# o_clone_rev_d.net
KiCad netlist of a schematic drawn in EAGLE
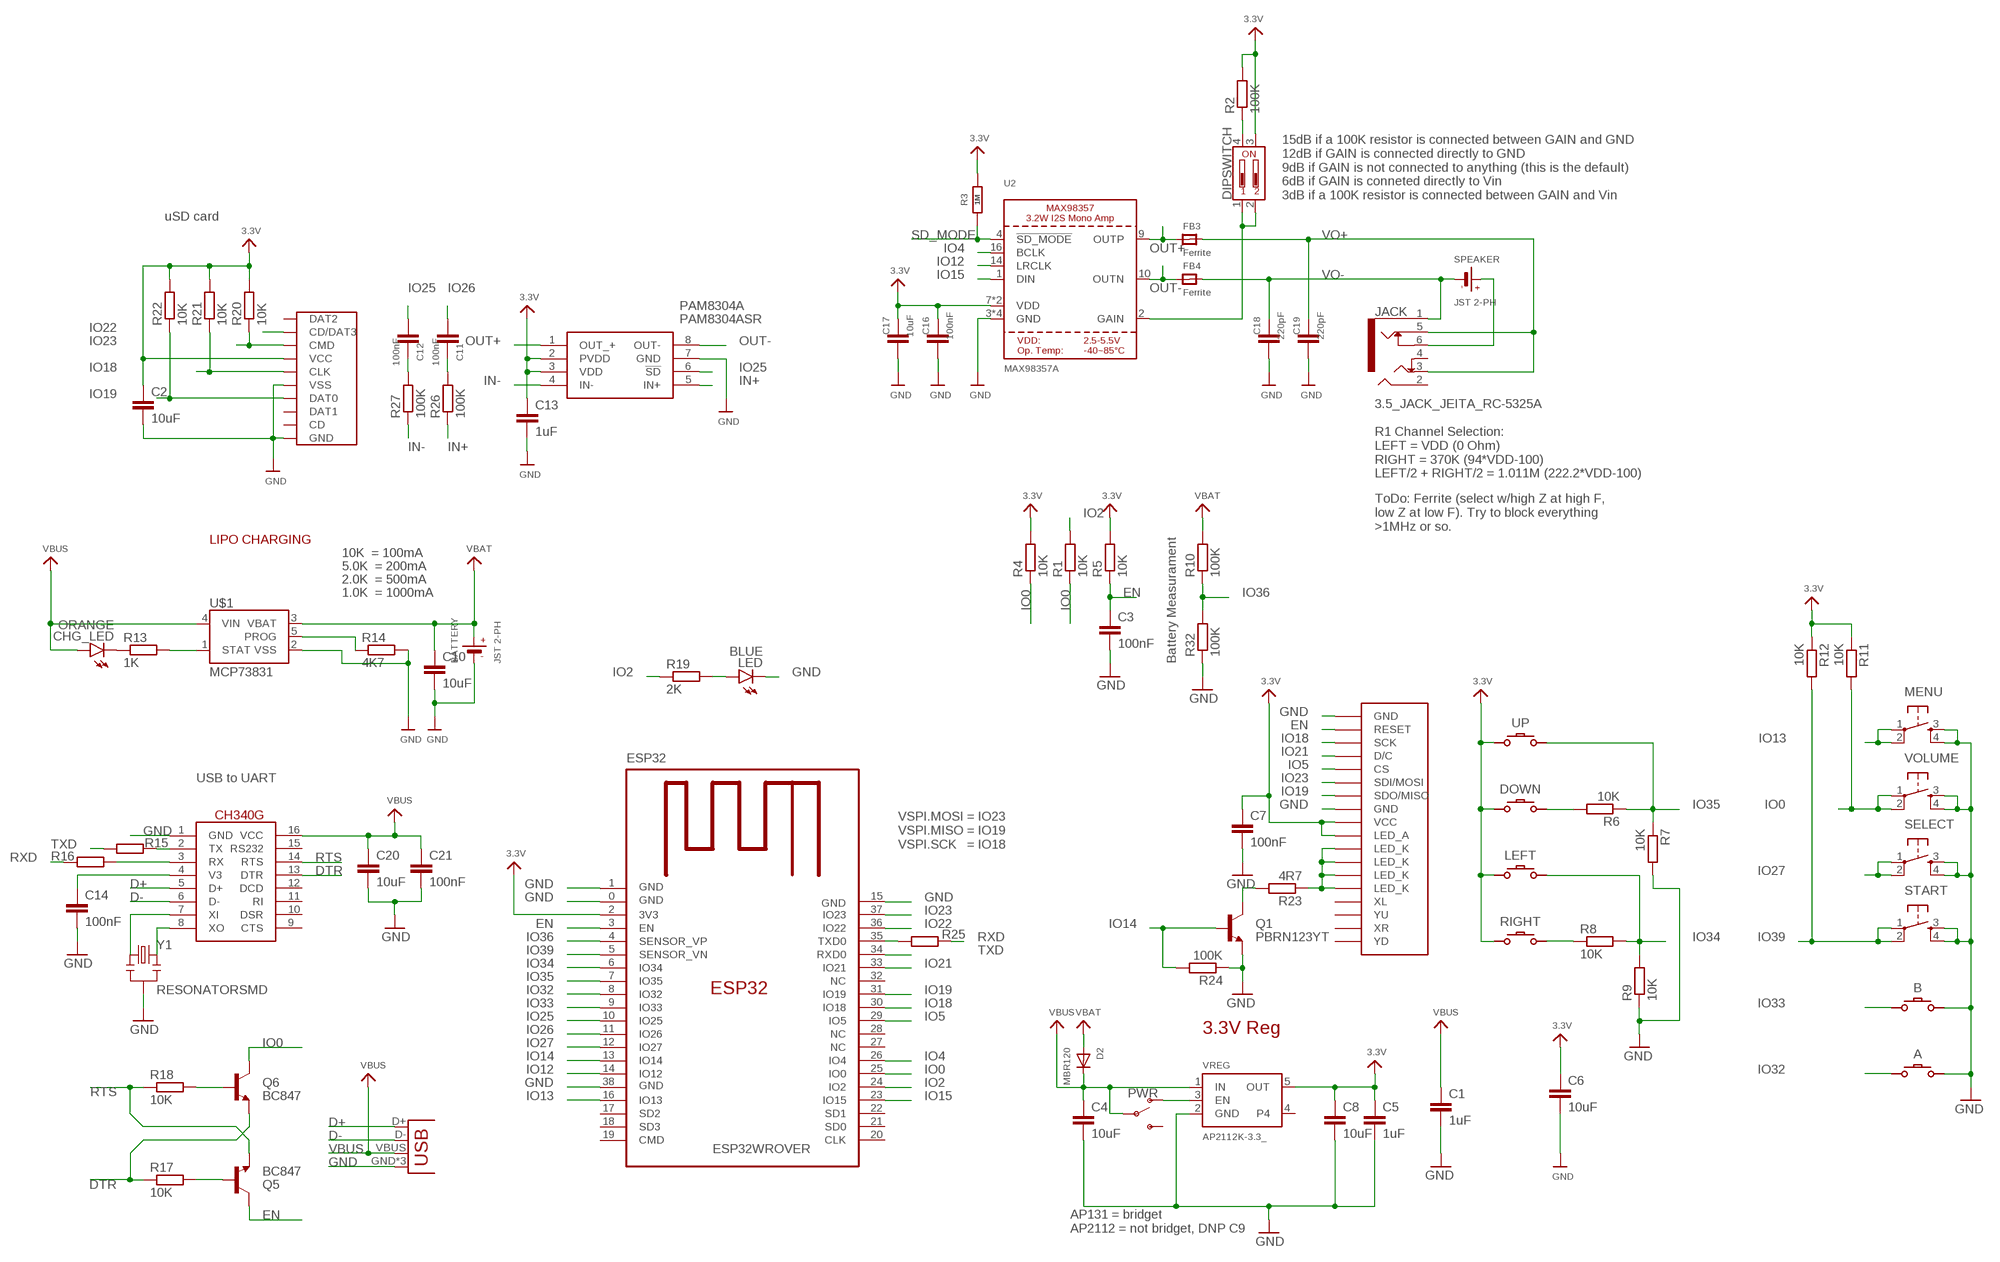
[diagram p0: schematic, sheet 1]

(export (version "E")
  (design (tool "Eeschema 10.0.6"))
  (components
    (comp (ref "A")
      (value "CONDUCTIVE_BUTTON")
      (footprint "eagle-import:CONDUCTIVE_BUTTON")
      (libsource (lib "eagle-import") (part "CONDUCTIVE_BUTTON"))
    )
    (comp (ref "B")
      (value "CONDUCTIVE_BUTTON")
      (footprint "eagle-import:CONDUCTIVE_BUTTON")
      (libsource (lib "eagle-import") (part "CONDUCTIVE_BUTTON"))
    )
    (comp (ref "BATTERY")
      (value "JST 2-PH")
      (footprint "eagle-import:JSTPH2")
      (libsource (lib "eagle-import") (part "JST_CONNECTOR"))
    )
    (comp (ref "C1")
      (value "1uF")
      (footprint "eagle-import:C0805K")
      (libsource (lib "eagle-import") (part "C-EUC0805K"))
    )
    (comp (ref "C2")
      (value "10uF")
      (footprint "eagle-import:C0805K")
      (libsource (lib "eagle-import") (part "C-EUC0805K"))
    )
    (comp (ref "C3")
      (value "100nF")
      (footprint "eagle-import:C0805K")
      (libsource (lib "eagle-import") (part "C-EUC0805K"))
    )
    (comp (ref "C4")
      (value "10uF")
      (footprint "eagle-import:C0805K")
      (libsource (lib "eagle-import") (part "C-EUC0805K"))
    )
    (comp (ref "C5")
      (value "1uF")
      (footprint "eagle-import:C0805K")
      (libsource (lib "eagle-import") (part "C-EUC0805K"))
    )
    (comp (ref "C6")
      (value "10uF")
      (footprint "eagle-import:C0805K")
      (libsource (lib "eagle-import") (part "C-EUC0805K"))
    )
    (comp (ref "C7")
      (value "100nF")
      (footprint "eagle-import:C0805")
      (libsource (lib "eagle-import") (part "C-EUC0805"))
    )
    (comp (ref "C8")
      (value "10uF")
      (footprint "eagle-import:C0805K")
      (libsource (lib "eagle-import") (part "C-EUC0805K"))
    )
    (comp (ref "C10")
      (value "10uF")
      (footprint "eagle-import:C0805K")
      (libsource (lib "eagle-import") (part "C-EUC0805K"))
    )
    (comp (ref "C11")
      (value "100nF")
      (footprint "eagle-import:C0805K")
      (libsource (lib "eagle-import") (part "C-EUC0805K"))
    )
    (comp (ref "C12")
      (value "100nF")
      (footprint "eagle-import:C0805K")
      (libsource (lib "eagle-import") (part "C-EUC0805K"))
    )
    (comp (ref "C13")
      (value "1uF")
      (footprint "eagle-import:C0805K")
      (libsource (lib "eagle-import") (part "C-EUC0805K"))
    )
    (comp (ref "C14")
      (value "100nF")
      (footprint "eagle-import:C0805K")
      (libsource (lib "eagle-import") (part "C-EUC0805K"))
    )
    (comp (ref "C16")
      (value "100nF")
      (footprint "eagle-import:C0805K")
      (libsource (lib "eagle-import") (part "C-EUC0805K"))
    )
    (comp (ref "C17")
      (value "10uF")
      (footprint "eagle-import:C0805K")
      (libsource (lib "eagle-import") (part "C-EUC0805K"))
    )
    (comp (ref "C18")
      (value "220pF")
      (footprint "eagle-import:C0805K")
      (libsource (lib "eagle-import") (part "C-EUC0805K"))
    )
    (comp (ref "C19")
      (value "220pF")
      (footprint "eagle-import:C0805K")
      (libsource (lib "eagle-import") (part "C-EUC0805K"))
    )
    (comp (ref "C20")
      (value "10uF")
      (footprint "eagle-import:C0805K")
      (libsource (lib "eagle-import") (part "C-EUC0805K"))
    )
    (comp (ref "C21")
      (value "100nF")
      (footprint "eagle-import:C0805K")
      (libsource (lib "eagle-import") (part "C-EUC0805K"))
    )
    (comp (ref "CHG_LED")
      (value "ORANGE")
      (footprint "eagle-import:CHIPLED_0805")
      (libsource (lib "eagle-import") (part "LEDCHIPLED_0805"))
    )
    (comp (ref "D2")
      (value "MBR120")
      (footprint "eagle-import:SOD-123")
      (libsource (lib "eagle-import") (part "DIODESOD-123"))
    )
    (comp (ref "DIPSWITCH")
      (value "DIP-02-SMD-50MIL")
      (footprint "eagle-import:DIPSWITCH-02-50MIL")
      (libsource (lib "eagle-import") (part "DIP-02-SMD-50MIL"))
    )
    (comp (ref "DOWN")
      (value "CONDUCTIVE_BUTTON")
      (footprint "eagle-import:CONDUCTIVE_BUTTON")
      (libsource (lib "eagle-import") (part "CONDUCTIVE_BUTTON"))
    )
    (comp (ref "ESP32")
      (value "ESP32WROVER")
      (footprint "eagle-import:ESP32WROVER")
      (libsource (lib "eagle-import") (part "ESP32WROVER"))
    )
    (comp (ref "FB3")
      (value "Ferrite")
      (footprint "eagle-import:0805")
      (libsource (lib "eagle-import") (part "FERRITE0805"))
    )
    (comp (ref "FB4")
      (value "Ferrite")
      (footprint "eagle-import:0805")
      (libsource (lib "eagle-import") (part "FERRITE0805"))
    )
    (comp (ref "JACK")
      (value "3.5_JACK_JEITA_RC-5325A")
      (footprint "eagle-import:3.5_JACK_JEITA_RC-5325A")
      (libsource (lib "eagle-import") (part "3.5_JACK_JEITA_RC-5325A"))
    )
    (comp (ref "LCD")
      (value "ILI9341_3.2LCD_")
      (footprint "eagle-import:LI9341_3.2LCD")
      (libsource (lib "eagle-import") (part "ILI9341_3.2LCD_"))
    )
    (comp (ref "LED")
      (value "BLUE")
      (footprint "eagle-import:CHIPLED_0805")
      (libsource (lib "eagle-import") (part "LEDCHIPLED_0805"))
    )
    (comp (ref "LEFT")
      (value "CONDUCTIVE_BUTTON")
      (footprint "eagle-import:CONDUCTIVE_BUTTON")
      (libsource (lib "eagle-import") (part "CONDUCTIVE_BUTTON"))
    )
    (comp (ref "MENU")
      (value "TACTILE_SWITCHE_5X5_MICRO\"")
      (footprint "eagle-import:TACTILE_SWITCH_5X5_MICRO")
      (libsource (lib "eagle-import") (part "TACTILE_SWITCHE_5X5_MICRO{dblquote}"))
    )
    (comp (ref "PAM8304A")
      (value "PAM8304ASR")
      (footprint "eagle-import:SOP65P490X110-8N")
      (fields (field (name "MOUSER_PART_NUMBER") "621-PAM8304ASR"))
      (libsource (lib "eagle-import") (part "PAM8304ASR"))
    )
    (comp (ref "PWR")
      (value "SWITCH-SPDT-SMD-RIGHT-ANGLE")
      (footprint "eagle-import:SWITCH_SPST_SMD_A")
      (libsource (lib "eagle-import") (part "SWITCH-SPDT-SMD-RIGHT-ANGLE"))
    )
    (comp (ref "Q1")
      (value "PBRN123YT")
      (footprint "eagle-import:SOT23-3")
      (libsource (lib "eagle-import") (part "TRANSISTOR_NPNSOT23-3"))
    )
    (comp (ref "Q5")
      (value "BC847")
      (footprint "eagle-import:SOT23-3")
      (libsource (lib "eagle-import") (part "TRANSISTOR_NPNSOT23-3"))
    )
    (comp (ref "Q6")
      (value "BC847")
      (footprint "eagle-import:SOT23-3")
      (libsource (lib "eagle-import") (part "TRANSISTOR_NPNSOT23-3"))
    )
    (comp (ref "R1")
      (value "10K")
      (footprint "eagle-import:R0805")
      (libsource (lib "eagle-import") (part "R-EU_R0805"))
    )
    (comp (ref "R2")
      (value "100K")
      (footprint "eagle-import:R0805")
      (libsource (lib "eagle-import") (part "R-EU_R0805"))
    )
    (comp (ref "R3")
      (value "1M")
      (footprint "eagle-import:R0805")
      (libsource (lib "eagle-import") (part "R-EU_R0805"))
    )
    (comp (ref "R4")
      (value "10K")
      (footprint "eagle-import:R0805")
      (libsource (lib "eagle-import") (part "R-EU_R0805"))
    )
    (comp (ref "R5")
      (value "10K")
      (footprint "eagle-import:R0805")
      (libsource (lib "eagle-import") (part "R-EU_R0805"))
    )
    (comp (ref "R6")
      (value "10K")
      (footprint "eagle-import:R0805")
      (libsource (lib "eagle-import") (part "R-EU_R0805"))
    )
    (comp (ref "R7")
      (value "10K")
      (footprint "eagle-import:R0805")
      (libsource (lib "eagle-import") (part "R-EU_R0805"))
    )
    (comp (ref "R8")
      (value "10K")
      (footprint "eagle-import:R0805")
      (libsource (lib "eagle-import") (part "R-EU_R0805"))
    )
    (comp (ref "R9")
      (value "10K")
      (footprint "eagle-import:R0805")
      (libsource (lib "eagle-import") (part "R-EU_R0805"))
    )
    (comp (ref "R10")
      (value "100K")
      (footprint "eagle-import:R0805")
      (libsource (lib "eagle-import") (part "R-EU_R0805"))
    )
    (comp (ref "R11")
      (value "10K")
      (footprint "eagle-import:R0805")
      (libsource (lib "eagle-import") (part "R-EU_R0805"))
    )
    (comp (ref "R12")
      (value "10K")
      (footprint "eagle-import:R0805")
      (libsource (lib "eagle-import") (part "R-EU_R0805"))
    )
    (comp (ref "R13")
      (value "1K")
      (footprint "eagle-import:R0805")
      (libsource (lib "eagle-import") (part "R-EU_R0805"))
    )
    (comp (ref "R14")
      (value "4K7")
      (footprint "eagle-import:R0805")
      (libsource (lib "eagle-import") (part "R-EU_R0805"))
    )
    (comp (ref "R15")
      (value "470R")
      (footprint "eagle-import:R0805")
      (libsource (lib "eagle-import") (part "R-EU_R0805"))
    )
    (comp (ref "R16")
      (value "470R")
      (footprint "eagle-import:R0805")
      (libsource (lib "eagle-import") (part "R-EU_R0805"))
    )
    (comp (ref "R17")
      (value "10K")
      (footprint "eagle-import:R0805")
      (libsource (lib "eagle-import") (part "R-EU_R0805"))
    )
    (comp (ref "R18")
      (value "10K")
      (footprint "eagle-import:R0805")
      (libsource (lib "eagle-import") (part "R-EU_R0805"))
    )
    (comp (ref "R19")
      (value "2K")
      (footprint "eagle-import:R0805")
      (libsource (lib "eagle-import") (part "R-EU_R0805"))
    )
    (comp (ref "R20")
      (value "10K")
      (footprint "eagle-import:R0805")
      (libsource (lib "eagle-import") (part "R-EU_R0805"))
    )
    (comp (ref "R21")
      (value "10K")
      (footprint "eagle-import:R0805")
      (libsource (lib "eagle-import") (part "R-EU_R0805"))
    )
    (comp (ref "R22")
      (value "10K")
      (footprint "eagle-import:R0805")
      (libsource (lib "eagle-import") (part "R-EU_R0805"))
    )
    (comp (ref "R23")
      (value "4R7")
      (footprint "eagle-import:R0805")
      (libsource (lib "eagle-import") (part "R-EU_R0805"))
    )
    (comp (ref "R24")
      (value "100K")
      (footprint "eagle-import:R0805")
      (libsource (lib "eagle-import") (part "R-EU_R0805"))
    )
    (comp (ref "R25")
      (value "470R")
      (footprint "eagle-import:R0805")
      (libsource (lib "eagle-import") (part "R-EU_R0805"))
    )
    (comp (ref "R26")
      (value "100K")
      (footprint "eagle-import:R0805")
      (libsource (lib "eagle-import") (part "R-EU_R0805"))
    )
    (comp (ref "R27")
      (value "100K")
      (footprint "eagle-import:R0805")
      (libsource (lib "eagle-import") (part "R-EU_R0805"))
    )
    (comp (ref "R32")
      (value "100K")
      (footprint "eagle-import:R0805")
      (libsource (lib "eagle-import") (part "R-EU_R0805"))
    )
    (comp (ref "RIGHT")
      (value "CONDUCTIVE_BUTTON")
      (footprint "eagle-import:CONDUCTIVE_BUTTON")
      (libsource (lib "eagle-import") (part "CONDUCTIVE_BUTTON"))
    )
    (comp (ref "SD_CARD")
      (value "MICRO_SD_CARD\"")
      (footprint "eagle-import:TFP09-2--12B")
      (libsource (lib "eagle-import") (part "MICRO_SD_CARD{dblquote}"))
    )
    (comp (ref "SELECT")
      (value "TACTILE_SWITCHE_5X5_MICRO\"")
      (footprint "eagle-import:TACTILE_SWITCH_5X5_MICRO")
      (libsource (lib "eagle-import") (part "TACTILE_SWITCHE_5X5_MICRO{dblquote}"))
    )
    (comp (ref "SPEAKER")
      (value "JST 2-PH")
      (footprint "eagle-import:JSTPH2")
      (libsource (lib "eagle-import") (part "JST_CONNECTOR"))
    )
    (comp (ref "START")
      (value "TACTILE_SWITCHE_5X5_MICRO\"")
      (footprint "eagle-import:TACTILE_SWITCH_5X5_MICRO")
      (libsource (lib "eagle-import") (part "TACTILE_SWITCHE_5X5_MICRO{dblquote}"))
    )
    (comp (ref "U$1")
      (value "MCP73831")
      (footprint "eagle-import:SOT95P290X120-5")
      (libsource (lib "eagle-import") (part "MCP73831"))
    )
    (comp (ref "U$23")
      (value "CH340G")
      (footprint "eagle-import:SO16")
      (libsource (lib "eagle-import") (part "CH340G"))
    )
    (comp (ref "U2")
      (value "MAX98357A")
      (footprint "eagle-import:QFN16_3MM")
      (libsource (lib "eagle-import") (part "AUDIOAMP_MAX98357"))
    )
    (comp (ref "UP")
      (value "CONDUCTIVE_BUTTON")
      (footprint "eagle-import:CONDUCTIVE_BUTTON")
      (libsource (lib "eagle-import") (part "CONDUCTIVE_BUTTON"))
    )
    (comp (ref "USB")
      (value "USB_MICRO_ATTEND_")
      (footprint "eagle-import:USB_MICRO")
      (libsource (lib "eagle-import") (part "USB_MICRO_ATTEND_"))
    )
    (comp (ref "VOLUME")
      (value "TACTILE_SWITCHE_5X5_MICRO\"")
      (footprint "eagle-import:TACTILE_SWITCH_5X5_MICRO")
      (libsource (lib "eagle-import") (part "TACTILE_SWITCHE_5X5_MICRO{dblquote}"))
    )
    (comp (ref "VREG")
      (value "AP2112K-3.3_")
      (footprint "eagle-import:SOT95P290X120-5")
      (libsource (lib "eagle-import") (part "AP2112K-3.3_"))
    )
    (comp (ref "Y1")
      (value "RESONATORSMD")
      (footprint "eagle-import:RESONATOR-SMD")
      (libsource (lib "eagle-import") (part "RESONATORSMD"))
    )
  )
  (nets
    (net (code "1") (name "/D+") (class "Default")
      (node (ref "U$23") (pin "5") (pinfunction "D+_5") (pintype "bidirectional"))
      (node (ref "USB") (pin "D+") (pinfunction "D+_D+") (pintype "bidirectional"))
    )
    (net (code "2") (name "/D-") (class "Default")
      (node (ref "U$23") (pin "6") (pinfunction "D-_6") (pintype "bidirectional"))
      (node (ref "USB") (pin "D-") (pinfunction "D-_D-") (pintype "bidirectional"))
    )
    (net (code "3") (name "/DTR") (class "Default")
      (node (ref "Q6") (pin "2") (pinfunction "E_2") (pintype "passive"))
      (node (ref "R17") (pin "1") (pinfunction "1_1") (pintype "passive"))
      (node (ref "U$23") (pin "13") (pinfunction "DTR_13") (pintype "bidirectional"))
    )
    (net (code "4") (name "/EN") (class "Default")
      (node (ref "C3") (pin "1") (pinfunction "1_1") (pintype "passive"))
      (node (ref "ESP32") (pin "3") (pinfunction "EN_3") (pintype "bidirectional"))
      (node (ref "LCD") (pin "P$2") (pinfunction "RESET_P$2") (pintype "bidirectional"))
      (node (ref "Q5") (pin "3") (pinfunction "C_3") (pintype "passive"))
      (node (ref "R5") (pin "1") (pinfunction "1_1") (pintype "passive"))
    )
    (net (code "5") (name "/IN+") (class "Default")
      (node (ref "PAM8304A") (pin "5") (pinfunction "IN+_5") (pintype "bidirectional"))
      (node (ref "R26") (pin "1") (pinfunction "1_1") (pintype "passive"))
    )
    (net (code "6") (name "/IN-") (class "Default")
      (node (ref "PAM8304A") (pin "4") (pinfunction "IN-_4") (pintype "bidirectional"))
      (node (ref "R27") (pin "1") (pinfunction "1_1") (pintype "passive"))
    )
    (net (code "7") (name "/IO0") (class "Default")
      (node (ref "ESP32") (pin "25") (pinfunction "IO0_25") (pintype "bidirectional"))
      (node (ref "Q6") (pin "3") (pinfunction "C_3") (pintype "passive"))
      (node (ref "R1") (pin "1") (pinfunction "1_1") (pintype "passive"))
      (node (ref "R11") (pin "2") (pinfunction "2_2") (pintype "passive"))
      (node (ref "R4") (pin "1") (pinfunction "1_1") (pintype "passive"))
      (node (ref "VOLUME") (pin "1") (pinfunction "1_1") (pintype "passive"))
      (node (ref "VOLUME") (pin "2") (pinfunction "2_2") (pintype "passive"))
    )
    (net (code "8") (name "/IO2") (class "Default")
      (node (ref "ESP32") (pin "24") (pinfunction "IO2_24") (pintype "bidirectional"))
      (node (ref "R1") (pin "2") (pinfunction "2_2") (pintype "passive"))
      (node (ref "R19") (pin "1") (pinfunction "1_1") (pintype "passive"))
    )
    (net (code "9") (name "/IO4") (class "Default")
      (node (ref "ESP32") (pin "26") (pinfunction "IO4_26") (pintype "bidirectional"))
      (node (ref "U2") (pin "16") (pinfunction "BCLK_16") (pintype "bidirectional"))
    )
    (net (code "10") (name "/IO5") (class "Default")
      (node (ref "ESP32") (pin "29") (pinfunction "IO5_29") (pintype "bidirectional"))
      (node (ref "LCD") (pin "P$5") (pinfunction "CS_P$5") (pintype "bidirectional"))
    )
    (net (code "11") (name "/IO12") (class "Default")
      (node (ref "ESP32") (pin "14") (pinfunction "IO12_14") (pintype "bidirectional"))
      (node (ref "U2") (pin "14") (pinfunction "LRCLK_14") (pintype "bidirectional"))
    )
    (net (code "12") (name "/IO13") (class "Default")
      (node (ref "ESP32") (pin "16") (pinfunction "IO13_16") (pintype "bidirectional"))
      (node (ref "MENU") (pin "1") (pinfunction "1_1") (pintype "passive"))
      (node (ref "MENU") (pin "2") (pinfunction "2_2") (pintype "passive"))
    )
    (net (code "13") (name "/IO14") (class "Default")
      (node (ref "ESP32") (pin "13") (pinfunction "IO14_13") (pintype "bidirectional"))
      (node (ref "Q1") (pin "1") (pinfunction "B_1") (pintype "passive"))
      (node (ref "R24") (pin "2") (pinfunction "2_2") (pintype "passive"))
    )
    (net (code "14") (name "/IO15") (class "Default")
      (node (ref "ESP32") (pin "23") (pinfunction "IO15_23") (pintype "bidirectional"))
      (node (ref "U2") (pin "1") (pinfunction "DIN_1") (pintype "bidirectional"))
    )
    (net (code "15") (name "/IO18") (class "Default")
      (node (ref "ESP32") (pin "30") (pinfunction "IO18_30") (pintype "bidirectional"))
      (node (ref "LCD") (pin "P$3") (pinfunction "SCK_P$3") (pintype "bidirectional"))
      (node (ref "R21") (pin "1") (pinfunction "1_1") (pintype "passive"))
      (node (ref "SD_CARD") (pin "CLK") (pinfunction "CLK_CLK") (pintype "bidirectional"))
    )
    (net (code "16") (name "/IO19") (class "Default")
      (node (ref "ESP32") (pin "31") (pinfunction "IO19_31") (pintype "bidirectional"))
      (node (ref "LCD") (pin "P$7") (pinfunction "SDO/MISO_P$7") (pintype "bidirectional"))
      (node (ref "R22") (pin "1") (pinfunction "1_1") (pintype "passive"))
      (node (ref "SD_CARD") (pin "DAT0") (pinfunction "DAT0_DAT0") (pintype "bidirectional"))
    )
    (net (code "17") (name "/IO21") (class "Default")
      (node (ref "ESP32") (pin "33") (pinfunction "IO21_33") (pintype "bidirectional"))
      (node (ref "LCD") (pin "P$4") (pinfunction "D/C_P$4") (pintype "bidirectional"))
    )
    (net (code "18") (name "/IO22") (class "Default")
      (node (ref "ESP32") (pin "36") (pinfunction "IO22_36") (pintype "bidirectional"))
      (node (ref "SD_CARD") (pin "CD/DAT3") (pinfunction "CD/DAT3_CD/DAT3") (pintype "bidirectional"))
    )
    (net (code "19") (name "/IO23") (class "Default")
      (node (ref "ESP32") (pin "37") (pinfunction "IO23_37") (pintype "bidirectional"))
      (node (ref "LCD") (pin "P$6") (pinfunction "SDI/MOSI_P$6") (pintype "bidirectional"))
      (node (ref "R20") (pin "1") (pinfunction "1_1") (pintype "passive"))
      (node (ref "SD_CARD") (pin "CMD") (pinfunction "CMD_CMD") (pintype "bidirectional"))
    )
    (net (code "20") (name "/IO25") (class "Default")
      (node (ref "C12") (pin "2") (pinfunction "2_2") (pintype "passive"))
      (node (ref "ESP32") (pin "10") (pinfunction "IO25_10") (pintype "bidirectional"))
      (node (ref "PAM8304A") (pin "6") (pinfunction "~{SD}_6") (pintype "bidirectional"))
    )
    (net (code "21") (name "/IO26") (class "Default")
      (node (ref "C11") (pin "2") (pinfunction "2_2") (pintype "passive"))
      (node (ref "ESP32") (pin "11") (pinfunction "IO26_11") (pintype "bidirectional"))
    )
    (net (code "22") (name "/IO27") (class "Default")
      (node (ref "ESP32") (pin "12") (pinfunction "IO27_12") (pintype "bidirectional"))
      (node (ref "SELECT") (pin "1") (pinfunction "1_1") (pintype "passive"))
      (node (ref "SELECT") (pin "2") (pinfunction "2_2") (pintype "passive"))
    )
    (net (code "23") (name "/IO32") (class "Default")
      (node (ref "A") (pin "P$1") (pinfunction "P$1_P$1") (pintype "bidirectional"))
      (node (ref "ESP32") (pin "8") (pinfunction "IO32_8") (pintype "bidirectional"))
    )
    (net (code "24") (name "/IO33") (class "Default")
      (node (ref "B") (pin "P$1") (pinfunction "P$1_P$1") (pintype "bidirectional"))
      (node (ref "ESP32") (pin "9") (pinfunction "IO33_9") (pintype "bidirectional"))
    )
    (net (code "25") (name "/IO34") (class "Default")
      (node (ref "ESP32") (pin "6") (pinfunction "IO34_6") (pintype "bidirectional"))
      (node (ref "LEFT") (pin "P$2") (pinfunction "P$2_P$2") (pintype "bidirectional"))
      (node (ref "R8") (pin "2") (pinfunction "2_2") (pintype "passive"))
      (node (ref "R9") (pin "2") (pinfunction "2_2") (pintype "passive"))
    )
    (net (code "26") (name "/IO35") (class "Default")
      (node (ref "ESP32") (pin "7") (pinfunction "IO35_7") (pintype "bidirectional"))
      (node (ref "R6") (pin "1") (pinfunction "1_1") (pintype "passive"))
      (node (ref "R7") (pin "1") (pinfunction "1_1") (pintype "passive"))
      (node (ref "UP") (pin "P$2") (pinfunction "P$2_P$2") (pintype "bidirectional"))
    )
    (net (code "27") (name "/IO36") (class "Default")
      (node (ref "ESP32") (pin "4") (pinfunction "SENSOR_VP_4") (pintype "bidirectional"))
      (node (ref "R10") (pin "1") (pinfunction "1_1") (pintype "passive"))
      (node (ref "R32") (pin "2") (pinfunction "2_2") (pintype "passive"))
    )
    (net (code "28") (name "/IO39") (class "Default")
      (node (ref "ESP32") (pin "5") (pinfunction "SENSOR_VN_5") (pintype "bidirectional"))
      (node (ref "R12") (pin "2") (pinfunction "2_2") (pintype "passive"))
      (node (ref "START") (pin "1") (pinfunction "1_1") (pintype "passive"))
      (node (ref "START") (pin "2") (pinfunction "2_2") (pintype "passive"))
    )
    (net (code "29") (name "/OUT+") (class "Default")
      (node (ref "FB3") (pin "1") (pinfunction "P$1_1") (pintype "passive"))
      (node (ref "PAM8304A") (pin "1") (pinfunction "OUT_+_1") (pintype "bidirectional"))
      (node (ref "U2") (pin "9") (pinfunction "OUTP_9") (pintype "output"))
    )
    (net (code "30") (name "/OUT-") (class "Default")
      (node (ref "FB4") (pin "1") (pinfunction "P$1_1") (pintype "passive"))
      (node (ref "PAM8304A") (pin "8") (pinfunction "OUT-_8") (pintype "bidirectional"))
      (node (ref "U2") (pin "10") (pinfunction "OUTN_10") (pintype "output"))
    )
    (net (code "31") (name "/RTS") (class "Default")
      (node (ref "Q5") (pin "2") (pinfunction "E_2") (pintype "passive"))
      (node (ref "R18") (pin "1") (pinfunction "1_1") (pintype "passive"))
      (node (ref "U$23") (pin "14") (pinfunction "RTS_14") (pintype "bidirectional"))
    )
    (net (code "32") (name "/RXD") (class "Default")
      (node (ref "R16") (pin "2") (pinfunction "2_2") (pintype "passive"))
      (node (ref "R25") (pin "1") (pinfunction "1_1") (pintype "passive"))
    )
    (net (code "33") (name "/SD_MODE") (class "Default")
      (node (ref "R3") (pin "1") (pinfunction "1_1") (pintype "passive"))
      (node (ref "U2") (pin "4") (pinfunction "~{SD_MODE}_4") (pintype "bidirectional"))
    )
    (net (code "34") (name "/TXD") (class "Default")
      (node (ref "ESP32") (pin "34") (pinfunction "RXD0_34") (pintype "bidirectional"))
      (node (ref "R15") (pin "2") (pinfunction "2_2") (pintype "passive"))
    )
    (net (code "35") (name "/VO+") (class "Default")
      (node (ref "C19") (pin "1") (pinfunction "1_1") (pintype "passive"))
      (node (ref "FB3") (pin "2") (pinfunction "P$2_2") (pintype "passive"))
      (node (ref "JACK") (pin "3") (pinfunction "3_3") (pintype "bidirectional"))
      (node (ref "JACK") (pin "5") (pinfunction "5_5") (pintype "bidirectional"))
    )
    (net (code "36") (name "/VO-") (class "Default")
      (node (ref "C18") (pin "1") (pinfunction "1_1") (pintype "passive"))
      (node (ref "FB4") (pin "2") (pinfunction "P$2_2") (pintype "passive"))
      (node (ref "JACK") (pin "1") (pinfunction "1_1") (pintype "bidirectional"))
      (node (ref "SPEAKER") (pin "1") (pinfunction "-_1") (pintype "passive"))
    )
    (net (code "37") (name "3.3V") (class "Default")
      (node (ref "C13") (pin "1") (pinfunction "1_1") (pintype "passive"))
      (node (ref "C16") (pin "1") (pinfunction "1_1") (pintype "passive"))
      (node (ref "C17") (pin "1") (pinfunction "1_1") (pintype "passive"))
      (node (ref "C2") (pin "1") (pinfunction "1_1") (pintype "passive"))
      (node (ref "C5") (pin "1") (pinfunction "1_1") (pintype "passive"))
      (node (ref "C6") (pin "1") (pinfunction "1_1") (pintype "passive"))
      (node (ref "C7") (pin "1") (pinfunction "1_1") (pintype "passive"))
      (node (ref "C8") (pin "1") (pinfunction "1_1") (pintype "passive"))
      (node (ref "DIPSWITCH") (pin "3") (pinfunction "P$3_3") (pintype "bidirectional"))
      (node (ref "DOWN") (pin "P$1") (pinfunction "P$1_P$1") (pintype "bidirectional"))
      (node (ref "ESP32") (pin "2") (pinfunction "3V3_2") (pintype "power_in"))
      (node (ref "LCD") (pin "P$10") (pinfunction "LED_A_P$10") (pintype "bidirectional"))
      (node (ref "LCD") (pin "P$9") (pinfunction "VCC_P$9") (pintype "bidirectional"))
      (node (ref "LEFT") (pin "P$1") (pinfunction "P$1_P$1") (pintype "bidirectional"))
      (node (ref "PAM8304A") (pin "2") (pinfunction "PVDD_2") (pintype "bidirectional"))
      (node (ref "PAM8304A") (pin "3") (pinfunction "VDD_3") (pintype "bidirectional"))
      (node (ref "R11") (pin "1") (pinfunction "1_1") (pintype "passive"))
      (node (ref "R12") (pin "1") (pinfunction "1_1") (pintype "passive"))
      (node (ref "R2") (pin "2") (pinfunction "2_2") (pintype "passive"))
      (node (ref "R20") (pin "2") (pinfunction "2_2") (pintype "passive"))
      (node (ref "R21") (pin "2") (pinfunction "2_2") (pintype "passive"))
      (node (ref "R22") (pin "2") (pinfunction "2_2") (pintype "passive"))
      (node (ref "R3") (pin "2") (pinfunction "2_2") (pintype "passive"))
      (node (ref "R4") (pin "2") (pinfunction "2_2") (pintype "passive"))
      (node (ref "R5") (pin "2") (pinfunction "2_2") (pintype "passive"))
      (node (ref "RIGHT") (pin "P$1") (pinfunction "P$1_P$1") (pintype "bidirectional"))
      (node (ref "SD_CARD") (pin "VCC") (pinfunction "VCC_VCC") (pintype "bidirectional"))
      (node (ref "U2") (pin "7") (pinfunction "VDD_7") (pintype "power_in"))
      (node (ref "U2") (pin "8") (pinfunction "VDD_8") (pintype "power_in"))
      (node (ref "UP") (pin "P$1") (pinfunction "P$1_P$1") (pintype "bidirectional"))
      (node (ref "VREG") (pin "5") (pinfunction "OUT_5") (pintype "bidirectional"))
    )
    (net (code "38") (name "GND") (class "Default")
      (node (ref "A") (pin "P$2") (pinfunction "P$2_P$2") (pintype "bidirectional"))
      (node (ref "B") (pin "P$2") (pinfunction "P$2_P$2") (pintype "bidirectional"))
      (node (ref "BATTERY") (pin "1") (pinfunction "-_1") (pintype "passive"))
      (node (ref "C1") (pin "2") (pinfunction "2_2") (pintype "passive"))
      (node (ref "C10") (pin "2") (pinfunction "2_2") (pintype "passive"))
      (node (ref "C13") (pin "2") (pinfunction "2_2") (pintype "passive"))
      (node (ref "C14") (pin "2") (pinfunction "2_2") (pintype "passive"))
      (node (ref "C16") (pin "2") (pinfunction "2_2") (pintype "passive"))
      (node (ref "C17") (pin "2") (pinfunction "2_2") (pintype "passive"))
      (node (ref "C18") (pin "2") (pinfunction "2_2") (pintype "passive"))
      (node (ref "C19") (pin "2") (pinfunction "2_2") (pintype "passive"))
      (node (ref "C2") (pin "2") (pinfunction "2_2") (pintype "passive"))
      (node (ref "C20") (pin "2") (pinfunction "2_2") (pintype "passive"))
      (node (ref "C21") (pin "2") (pinfunction "2_2") (pintype "passive"))
      (node (ref "C3") (pin "2") (pinfunction "2_2") (pintype "passive"))
      (node (ref "C4") (pin "2") (pinfunction "2_2") (pintype "passive"))
      (node (ref "C5") (pin "2") (pinfunction "2_2") (pintype "passive"))
      (node (ref "C6") (pin "2") (pinfunction "2_2") (pintype "passive"))
      (node (ref "C7") (pin "2") (pinfunction "2_2") (pintype "passive"))
      (node (ref "C8") (pin "2") (pinfunction "2_2") (pintype "passive"))
      (node (ref "ESP32") (pin "0") (pinfunction "GND_0") (pintype "power_in"))
      (node (ref "ESP32") (pin "1") (pinfunction "GND_1") (pintype "power_in"))
      (node (ref "ESP32") (pin "15") (pinfunction "GND_15") (pintype "power_in"))
      (node (ref "ESP32") (pin "38") (pinfunction "GND_38") (pintype "power_in"))
      (node (ref "LCD") (pin "P$1") (pinfunction "GND_P$1") (pintype "bidirectional"))
      (node (ref "LCD") (pin "P$8") (pinfunction "GND_P$8") (pintype "bidirectional"))
      (node (ref "LED") (pin "C") (pinfunction "C_C") (pintype "passive"))
      (node (ref "MENU") (pin "3") (pinfunction "3_3") (pintype "passive"))
      (node (ref "MENU") (pin "4") (pinfunction "4_4") (pintype "passive"))
      (node (ref "PAM8304A") (pin "7") (pinfunction "GND_7") (pintype "bidirectional"))
      (node (ref "Q1") (pin "2") (pinfunction "E_2") (pintype "passive"))
      (node (ref "R14") (pin "2") (pinfunction "2_2") (pintype "passive"))
      (node (ref "R24") (pin "1") (pinfunction "1_1") (pintype "passive"))
      (node (ref "R32") (pin "1") (pinfunction "1_1") (pintype "passive"))
      (node (ref "R7") (pin "2") (pinfunction "2_2") (pintype "passive"))
      (node (ref "R9") (pin "1") (pinfunction "1_1") (pintype "passive"))
      (node (ref "SD_CARD") (pin "GND") (pinfunction "GND_GND") (pintype "bidirectional"))
      (node (ref "SD_CARD") (pin "GND@1") (pinfunction "GND_GND@1") (pintype "bidirectional"))
      (node (ref "SD_CARD") (pin "GND@2") (pinfunction "GND_GND@2") (pintype "bidirectional"))
      (node (ref "SD_CARD") (pin "GND@3") (pinfunction "VSS_GND@3") (pintype "bidirectional"))
      (node (ref "SD_CARD") (pin "VSS") (pinfunction "GND_VSS") (pintype "bidirectional"))
      (node (ref "SELECT") (pin "3") (pinfunction "3_3") (pintype "passive"))
      (node (ref "SELECT") (pin "4") (pinfunction "4_4") (pintype "passive"))
      (node (ref "START") (pin "3") (pinfunction "3_3") (pintype "passive"))
      (node (ref "START") (pin "4") (pinfunction "4_4") (pintype "passive"))
      (node (ref "U$1") (pin "2") (pinfunction "VSS_2") (pintype "power_in"))
      (node (ref "U$23") (pin "1") (pinfunction "GND_1") (pintype "bidirectional"))
      (node (ref "U2") (pin "11") (pinfunction "GND_11") (pintype "power_in"))
      (node (ref "U2") (pin "15") (pinfunction "GND_15") (pintype "power_in"))
      (node (ref "U2") (pin "3") (pinfunction "GND_3") (pintype "power_in"))
      (node (ref "U2") (pin "THERMAL") (pinfunction "GND_THERMAL") (pintype "power_in"))
      (node (ref "USB") (pin "GND") (pinfunction "GND_GND") (pintype "bidirectional"))
      (node (ref "USB") (pin "GND@2") (pinfunction "GND_GND@2") (pintype "bidirectional"))
      (node (ref "USB") (pin "GND@3") (pinfunction "GND_GND@3") (pintype "bidirectional"))
      (node (ref "VOLUME") (pin "3") (pinfunction "3_3") (pintype "passive"))
      (node (ref "VOLUME") (pin "4") (pinfunction "4_4") (pintype "passive"))
      (node (ref "VREG") (pin "2") (pinfunction "GND_2") (pintype "bidirectional"))
      (node (ref "Y1") (pin "2") (pinfunction "2_2") (pintype "passive"))
    )
    (net (code "39") (name "Net-(C11-Pad1)") (class "Default")
      (node (ref "C11") (pin "1") (pinfunction "1_1") (pintype "passive"))
      (node (ref "R26") (pin "2") (pinfunction "2_2") (pintype "passive"))
    )
    (net (code "40") (name "Net-(C12-Pad1)") (class "Default")
      (node (ref "C12") (pin "1") (pinfunction "1_1") (pintype "passive"))
      (node (ref "R27") (pin "2") (pinfunction "2_2") (pintype "passive"))
    )
    (net (code "41") (name "Net-(CHG_LED-PadC)") (class "Default")
      (node (ref "CHG_LED") (pin "C") (pinfunction "C_C") (pintype "passive"))
      (node (ref "R13") (pin "1") (pinfunction "1_1") (pintype "passive"))
    )
    (net (code "42") (name "Net-(DIPSWITCH-P$1)") (class "Default")
      (node (ref "DIPSWITCH") (pin "1") (pinfunction "P$1_1") (pintype "bidirectional"))
      (node (ref "DIPSWITCH") (pin "2") (pinfunction "P$2_2") (pintype "bidirectional"))
      (node (ref "U2") (pin "2") (pinfunction "GAIN_2") (pintype "bidirectional"))
    )
    (net (code "43") (name "Net-(DIPSWITCH-P$4)") (class "Default")
      (node (ref "DIPSWITCH") (pin "4") (pinfunction "P$4_4") (pintype "bidirectional"))
      (node (ref "R2") (pin "1") (pinfunction "1_1") (pintype "passive"))
    )
    (net (code "44") (name "Net-(DOWN-PadP$2)") (class "Default")
      (node (ref "DOWN") (pin "P$2") (pinfunction "P$2_P$2") (pintype "bidirectional"))
      (node (ref "R6") (pin "2") (pinfunction "2_2") (pintype "passive"))
    )
    (net (code "45") (name "Net-(ESP32-TXD0)") (class "Default")
      (node (ref "ESP32") (pin "35") (pinfunction "TXD0_35") (pintype "bidirectional"))
      (node (ref "R25") (pin "2") (pinfunction "2_2") (pintype "passive"))
    )
    (net (code "46") (name "Net-(LCD-LED_K-PadP$11)") (class "Default")
      (node (ref "LCD") (pin "P$11") (pinfunction "LED_K_P$11") (pintype "bidirectional"))
      (node (ref "LCD") (pin "P$12") (pinfunction "LED_K_P$12") (pintype "bidirectional"))
      (node (ref "LCD") (pin "P$13") (pinfunction "LED_K_P$13") (pintype "bidirectional"))
      (node (ref "LCD") (pin "P$14") (pinfunction "LED_K_P$14") (pintype "bidirectional"))
      (node (ref "R23") (pin "1") (pinfunction "1_1") (pintype "passive"))
    )
    (net (code "47") (name "Net-(LED-PadA)") (class "Default")
      (node (ref "LED") (pin "A") (pinfunction "A_A") (pintype "passive"))
      (node (ref "R19") (pin "2") (pinfunction "2_2") (pintype "passive"))
    )
    (net (code "48") (name "Net-(PWR-O)") (class "Default")
      (node (ref "PWR") (pin "1") (pinfunction "O_1") (pintype "passive"))
      (node (ref "VREG") (pin "3") (pinfunction "EN_3") (pintype "bidirectional"))
    )
    (net (code "49") (name "Net-(Q1-C)") (class "Default")
      (node (ref "Q1") (pin "3") (pinfunction "C_3") (pintype "passive"))
      (node (ref "R23") (pin "2") (pinfunction "2_2") (pintype "passive"))
    )
    (net (code "50") (name "Net-(Q5-B)") (class "Default")
      (node (ref "Q5") (pin "1") (pinfunction "B_1") (pintype "passive"))
      (node (ref "R17") (pin "2") (pinfunction "2_2") (pintype "passive"))
    )
    (net (code "51") (name "Net-(Q6-B)") (class "Default")
      (node (ref "Q6") (pin "1") (pinfunction "B_1") (pintype "passive"))
      (node (ref "R18") (pin "2") (pinfunction "2_2") (pintype "passive"))
    )
    (net (code "52") (name "Net-(R8-Pad1)") (class "Default")
      (node (ref "R8") (pin "1") (pinfunction "1_1") (pintype "passive"))
      (node (ref "RIGHT") (pin "P$2") (pinfunction "P$2_P$2") (pintype "bidirectional"))
    )
    (net (code "53") (name "Net-(SPEAKER-+)") (class "Default")
      (node (ref "JACK") (pin "6") (pinfunction "6_6") (pintype "bidirectional"))
      (node (ref "SPEAKER") (pin "2") (pinfunction "+_2") (pintype "passive"))
    )
    (net (code "54") (name "Net-(U$1-PROG)") (class "Default")
      (node (ref "R14") (pin "1") (pinfunction "1_1") (pintype "passive"))
      (node (ref "U$1") (pin "5") (pinfunction "PROG_5") (pintype "input"))
    )
    (net (code "55") (name "Net-(U$1-STAT)") (class "Default")
      (node (ref "R13") (pin "2") (pinfunction "2_2") (pintype "passive"))
      (node (ref "U$1") (pin "1") (pinfunction "STAT_1") (pintype "output"))
    )
    (net (code "56") (name "Net-(U$23-RX)") (class "Default")
      (node (ref "R16") (pin "1") (pinfunction "1_1") (pintype "passive"))
      (node (ref "U$23") (pin "3") (pinfunction "RX_3") (pintype "bidirectional"))
    )
    (net (code "57") (name "Net-(U$23-TX)") (class "Default")
      (node (ref "R15") (pin "1") (pinfunction "1_1") (pintype "passive"))
      (node (ref "U$23") (pin "2") (pinfunction "TX_2") (pintype "bidirectional"))
    )
    (net (code "58") (name "Net-(U$23-V3)") (class "Default")
      (node (ref "C14") (pin "1") (pinfunction "1_1") (pintype "passive"))
      (node (ref "U$23") (pin "4") (pinfunction "V3_4") (pintype "bidirectional"))
    )
    (net (code "59") (name "Net-(U$23-XI)") (class "Default")
      (node (ref "U$23") (pin "7") (pinfunction "XI_7") (pintype "bidirectional"))
      (node (ref "Y1") (pin "1") (pinfunction "1_1") (pintype "passive"))
    )
    (net (code "60") (name "Net-(U$23-XO)") (class "Default")
      (node (ref "U$23") (pin "8") (pinfunction "XO_8") (pintype "bidirectional"))
      (node (ref "Y1") (pin "3") (pinfunction "3_3") (pintype "passive"))
    )
    (net (code "61") (name "VBAT") (class "Default")
      (node (ref "BATTERY") (pin "2") (pinfunction "+_2") (pintype "passive"))
      (node (ref "C10") (pin "1") (pinfunction "1_1") (pintype "passive"))
      (node (ref "D2") (pin "A") (pinfunction "A_A") (pintype "passive"))
      (node (ref "R10") (pin "2") (pinfunction "2_2") (pintype "passive"))
      (node (ref "U$1") (pin "3") (pinfunction "VBAT_3") (pintype "power_in"))
    )
    (net (code "62") (name "VBUS") (class "Default")
      (node (ref "C1") (pin "1") (pinfunction "1_1") (pintype "passive"))
      (node (ref "C20") (pin "1") (pinfunction "1_1") (pintype "passive"))
      (node (ref "C21") (pin "1") (pinfunction "1_1") (pintype "passive"))
      (node (ref "C4") (pin "1") (pinfunction "1_1") (pintype "passive"))
      (node (ref "CHG_LED") (pin "A") (pinfunction "A_A") (pintype "passive"))
      (node (ref "D2") (pin "C") (pinfunction "C_C") (pintype "passive"))
      (node (ref "PWR") (pin "2") (pinfunction "P_2") (pintype "passive"))
      (node (ref "U$1") (pin "4") (pinfunction "VIN_4") (pintype "power_in"))
      (node (ref "U$23") (pin "16") (pinfunction "VCC_16") (pintype "bidirectional"))
      (node (ref "USB") (pin "VBUS") (pinfunction "VBUS_VBUS") (pintype "bidirectional"))
      (node (ref "VREG") (pin "1") (pinfunction "IN_1") (pintype "bidirectional"))
    )
    (net (code "63") (name "unconnected-(ESP32-CLK-Pad20)") (class "Default")
      (node (ref "ESP32") (pin "20") (pinfunction "CLK_20") (pintype "bidirectional"))
    )
    (net (code "64") (name "unconnected-(ESP32-CMD-Pad19)") (class "Default")
      (node (ref "ESP32") (pin "19") (pinfunction "CMD_19") (pintype "bidirectional"))
    )
    (net (code "65") (name "unconnected-(ESP32-NC-Pad27)") (class "Default")
      (node (ref "ESP32") (pin "27") (pinfunction "NC_27") (pintype "bidirectional"))
    )
    (net (code "66") (name "unconnected-(ESP32-NC-Pad28)") (class "Default")
      (node (ref "ESP32") (pin "28") (pinfunction "NC_28") (pintype "bidirectional"))
    )
    (net (code "67") (name "unconnected-(ESP32-NC-Pad32)") (class "Default")
      (node (ref "ESP32") (pin "32") (pinfunction "NC_32") (pintype "bidirectional"))
    )
    (net (code "68") (name "unconnected-(ESP32-SD0-Pad21)") (class "Default")
      (node (ref "ESP32") (pin "21") (pinfunction "SD0_21") (pintype "bidirectional"))
    )
    (net (code "69") (name "unconnected-(ESP32-SD1-Pad22)") (class "Default")
      (node (ref "ESP32") (pin "22") (pinfunction "SD1_22") (pintype "bidirectional"))
    )
    (net (code "70") (name "unconnected-(ESP32-SD2-Pad17)") (class "Default")
      (node (ref "ESP32") (pin "17") (pinfunction "SD2_17") (pintype "bidirectional"))
    )
    (net (code "71") (name "unconnected-(ESP32-SD3-Pad18)") (class "Default")
      (node (ref "ESP32") (pin "18") (pinfunction "SD3_18") (pintype "bidirectional"))
    )
    (net (code "72") (name "unconnected-(JACK-Pad2)") (class "Default")
      (node (ref "JACK") (pin "2") (pinfunction "2_2") (pintype "bidirectional"))
    )
    (net (code "73") (name "unconnected-(JACK-Pad4)") (class "Default")
      (node (ref "JACK") (pin "4") (pinfunction "4_4") (pintype "bidirectional"))
    )
    (net (code "74") (name "unconnected-(LCD-XL-PadP$15)") (class "Default")
      (node (ref "LCD") (pin "P$15") (pinfunction "XL_P$15") (pintype "bidirectional"))
    )
    (net (code "75") (name "unconnected-(LCD-XR-PadP$16)") (class "Default")
      (node (ref "LCD") (pin "P$16") (pinfunction "XR_P$16") (pintype "bidirectional"))
    )
    (net (code "76") (name "unconnected-(LCD-YD-PadP$17)") (class "Default")
      (node (ref "LCD") (pin "P$17") (pinfunction "YD_P$17") (pintype "bidirectional"))
    )
    (net (code "77") (name "unconnected-(LCD-YU-PadP$18)") (class "Default")
      (node (ref "LCD") (pin "P$18") (pinfunction "YU_P$18") (pintype "bidirectional"))
    )
    (net (code "78") (name "unconnected-(PWR-S-Pad3)") (class "Default")
      (node (ref "PWR") (pin "3") (pinfunction "S_3") (pintype "passive"))
    )
    (net (code "79") (name "unconnected-(SD_CARD-PadCD)") (class "Default")
      (node (ref "SD_CARD") (pin "CD") (pinfunction "CD_CD") (pintype "bidirectional"))
    )
    (net (code "80") (name "unconnected-(SD_CARD-PadDAT1)") (class "Default")
      (node (ref "SD_CARD") (pin "DAT1") (pinfunction "DAT1_DAT1") (pintype "bidirectional"))
    )
    (net (code "81") (name "unconnected-(SD_CARD-PadDAT2)") (class "Default")
      (node (ref "SD_CARD") (pin "DAT2") (pinfunction "DAT2_DAT2") (pintype "bidirectional"))
    )
    (net (code "82") (name "unconnected-(U$23-CTS-Pad9)") (class "Default")
      (node (ref "U$23") (pin "9") (pinfunction "CTS_9") (pintype "bidirectional"))
    )
    (net (code "83") (name "unconnected-(U$23-DCD-Pad12)") (class "Default")
      (node (ref "U$23") (pin "12") (pinfunction "DCD_12") (pintype "bidirectional"))
    )
    (net (code "84") (name "unconnected-(U$23-DSR-Pad10)") (class "Default")
      (node (ref "U$23") (pin "10") (pinfunction "DSR_10") (pintype "bidirectional"))
    )
    (net (code "85") (name "unconnected-(U$23-RI-Pad11)") (class "Default")
      (node (ref "U$23") (pin "11") (pinfunction "RI_11") (pintype "bidirectional"))
    )
    (net (code "86") (name "unconnected-(U$23-RS232-Pad15)") (class "Default")
      (node (ref "U$23") (pin "15") (pinfunction "RS232_15") (pintype "bidirectional"))
    )
    (net (code "87") (name "unconnected-(VREG-P4-Pad4)") (class "Default")
      (node (ref "VREG") (pin "4") (pinfunction "P4_4") (pintype "bidirectional"))
    )
  )
)
